# Maka_Niu_Endcap.net
KiCad netlist of a schematic drawn in EAGLE
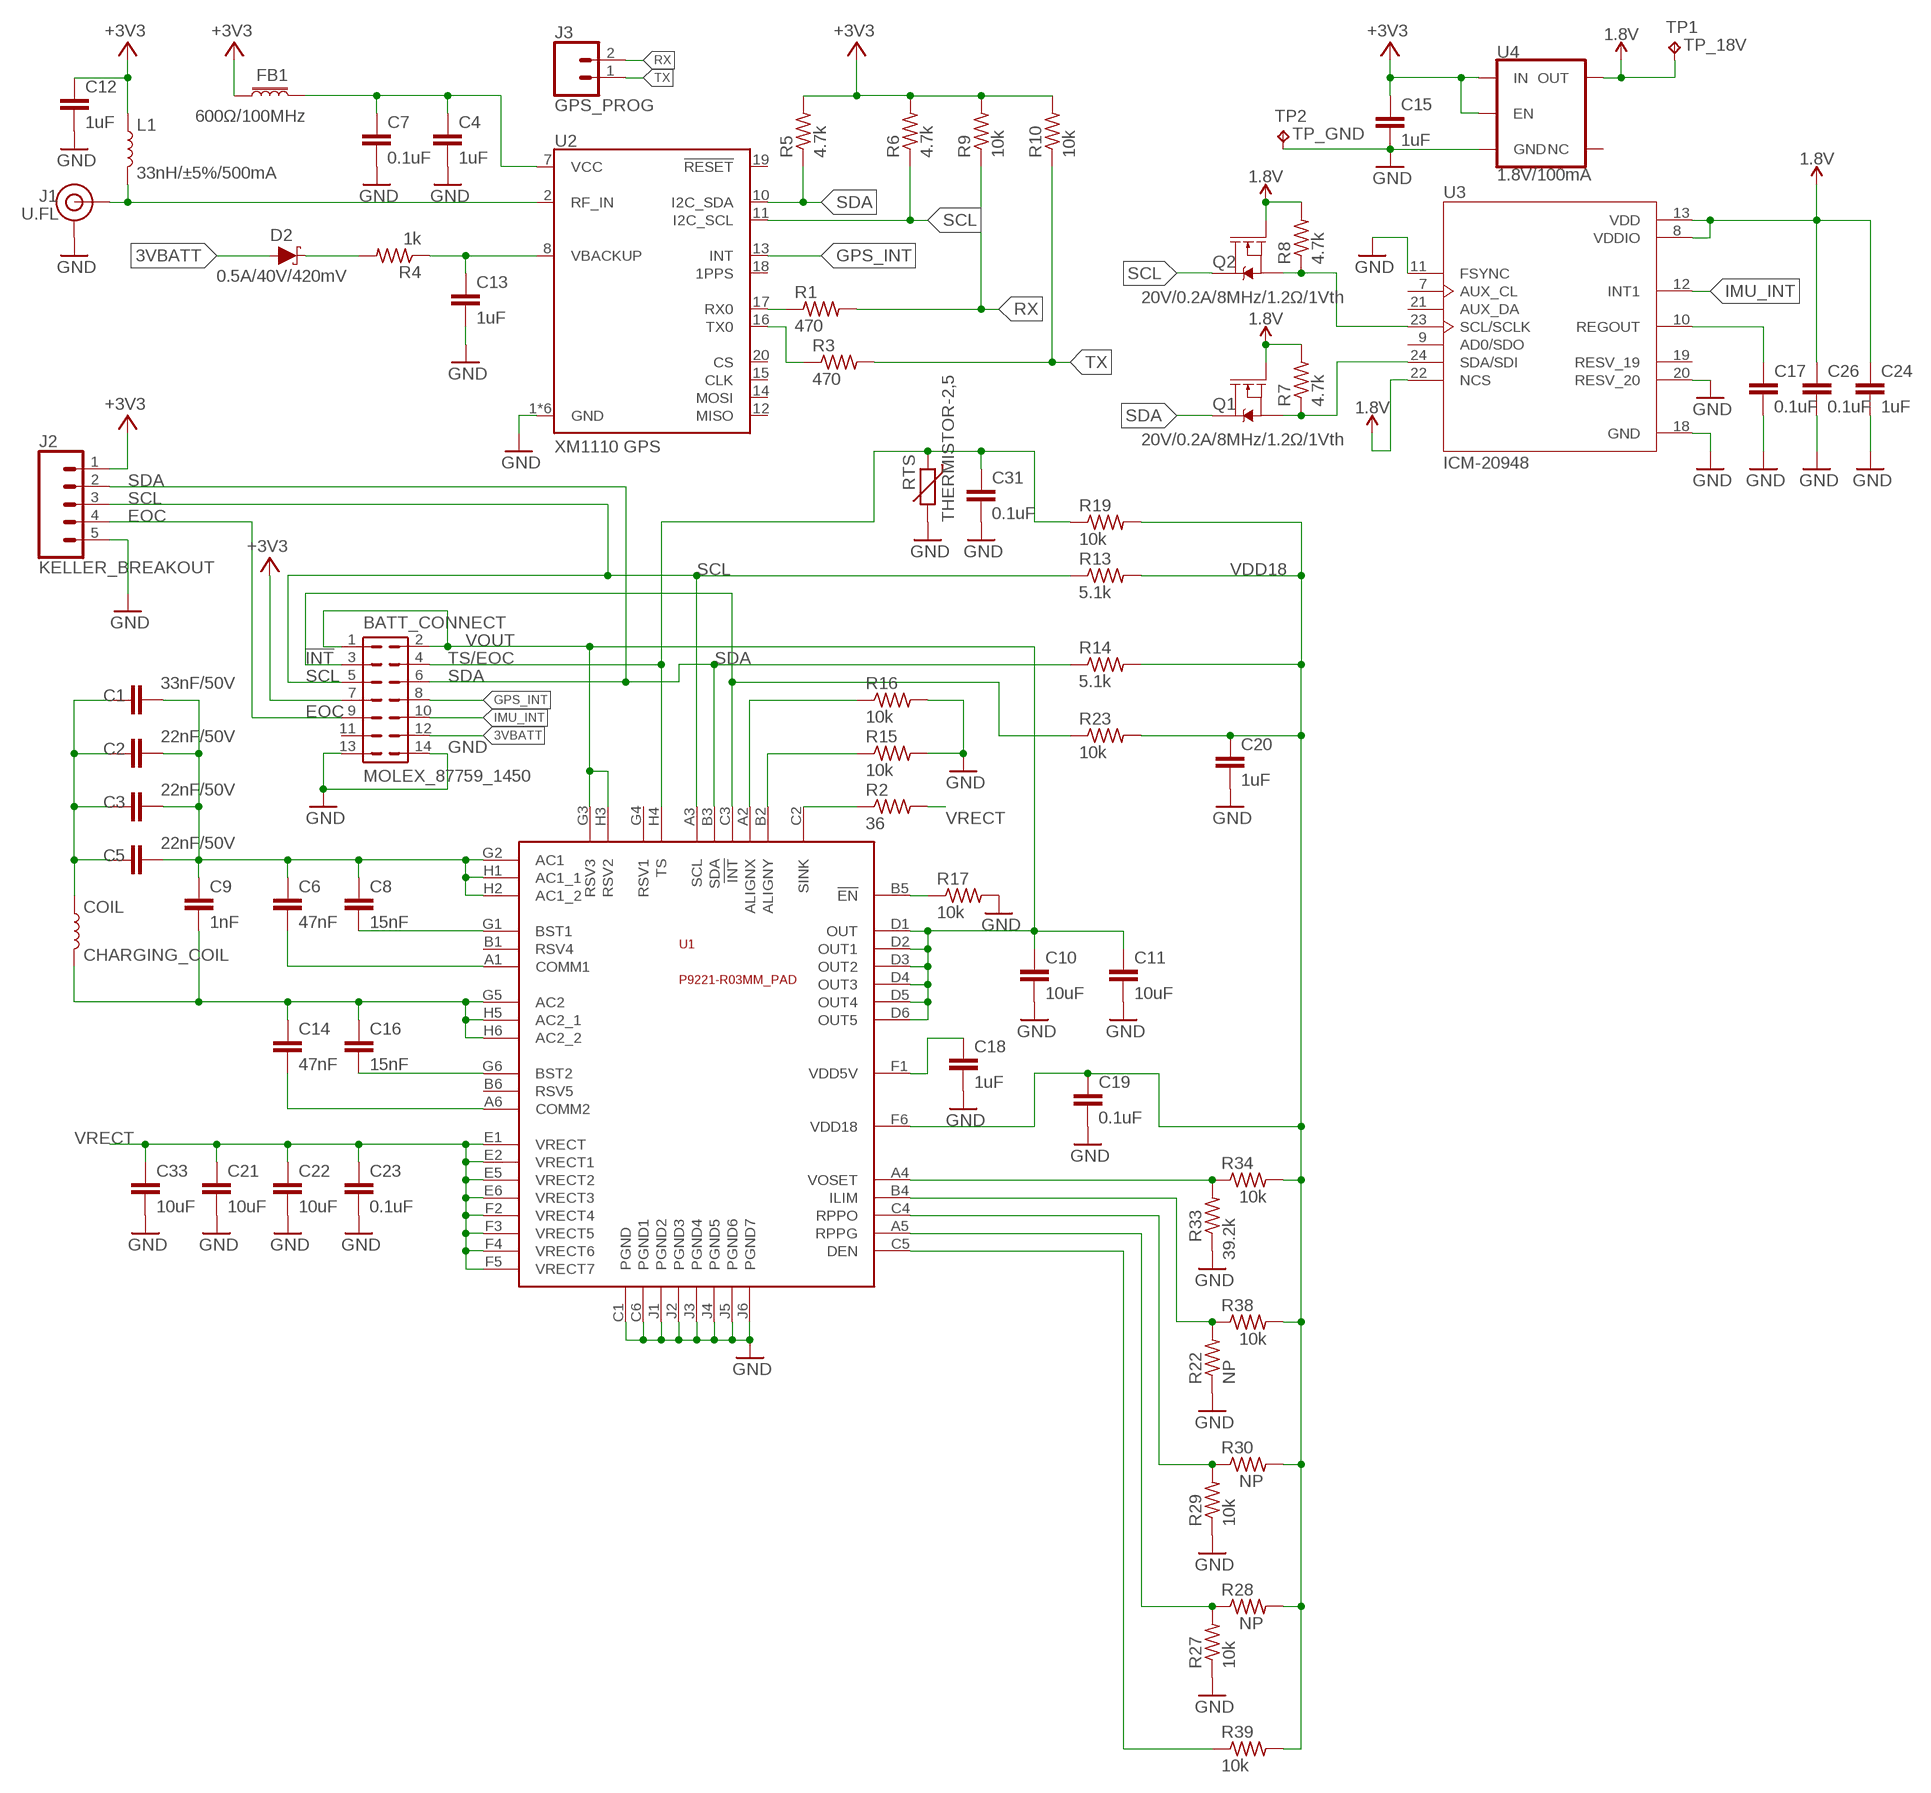
[diagram p0: schematic, sheet 1]

(export (version "E")
  (design (tool "Eeschema 10.0.6"))
  (components
    (comp (ref "BATT_CONNECT")
      (value "MOLEX_87759_1450")
      (footprint "eagle-import:87759-1450")
      (fields
        (field (name "DIGI-KEY_PART_NUMBER") "WM18654-ND")
        (field (name "MF") "MOLEX")
        (field (name "MP") "0877591450")
      )
      (libsource (lib "eagle-import") (part "MOLEX_87759_1450"))
    )
    (comp (ref "C1")
      (value "33nF/50V")
      (footprint "eagle-import:C0402")
      (fields
        (field (name "DIGI-KEY_PART_NUMBER") "490-13296-1-ND")
        (field (name "MF") "Murata Electronics")
        (field (name "MP") "GRM155R71H333KE02D")
      )
      (libsource (lib "eagle-import") (part "C-EUC0402"))
    )
    (comp (ref "C2")
      (value "22nF/50V")
      (footprint "eagle-import:C0402")
      (fields
        (field (name "DIGI-KEY_PART_NUMBER") "490-6360-1-ND")
        (field (name "MF") "Murata Electronics")
        (field (name "MP") "GRM155R71H223KA12J")
      )
      (libsource (lib "eagle-import") (part "C-EUC0402"))
    )
    (comp (ref "C3")
      (value "22nF/50V")
      (footprint "eagle-import:C0402")
      (fields
        (field (name "DIGI-KEY_PART_NUMBER") "490-6360-1-ND")
        (field (name "MF") "Murata Electronics")
        (field (name "MP") "GRM155R71H223KA12J")
      )
      (libsource (lib "eagle-import") (part "C-EUC0402"))
    )
    (comp (ref "C4")
      (value "1uF")
      (footprint "eagle-import:C0402")
      (fields
        (field (name "DIGI-KEY_PART_NUMBER") "311-1439-1-ND")
        (field (name "MF") "Yageo")
        (field (name "MP") "CC0402KRX5R6BB105")
      )
      (libsource (lib "eagle-import") (part "C-EUC0402"))
    )
    (comp (ref "C5")
      (value "22nF/50V")
      (footprint "eagle-import:C0402")
      (fields
        (field (name "DIGI-KEY_PART_NUMBER") "490-6360-1-ND")
        (field (name "MF") "Murata Electronics")
        (field (name "MP") "GRM155R71H223KA12J")
      )
      (libsource (lib "eagle-import") (part "C-EUC0402"))
    )
    (comp (ref "C6")
      (value "47nF")
      (footprint "eagle-import:C0402")
      (fields
        (field (name "DIGI-KEY_PART_NUMBER") "490-10702-1-ND")
        (field (name "MF") "Murata Electronics")
        (field (name "MP") "GRM155R71H473KE14D")
      )
      (libsource (lib "eagle-import") (part "C-EUC0402"))
    )
    (comp (ref "C7")
      (value "0.1uF")
      (footprint "eagle-import:C0402")
      (fields
        (field (name "DIGI-KEY_PART_NUMBER") "490-11917-1-ND")
        (field (name "MF") "Murata Electronics")
        (field (name "MP") "GRM155R61H104KE19D")
      )
      (libsource (lib "eagle-import") (part "C-EUC0402"))
    )
    (comp (ref "C8")
      (value "15nF")
      (footprint "eagle-import:C0402")
      (fields
        (field (name "DIGI-KEY_PART_NUMBER") "490-16428-1-ND")
        (field (name "MF") "Murata Electronics")
        (field (name "MP") "GCM155R71H153JA55D")
      )
      (libsource (lib "eagle-import") (part "C-EUC0402"))
    )
    (comp (ref "C9")
      (value "1nF")
      (footprint "eagle-import:C0402")
      (fields
        (field (name "DIGI-KEY_PART_NUMBER") "732-7556-1-ND")
        (field (name "MF") "Würth Elektronik")
        (field (name "MP") "885012205061 ")
      )
      (libsource (lib "eagle-import") (part "C-EUC0402"))
    )
    (comp (ref "C10")
      (value "10uF")
      (footprint "eagle-import:C_0603")
      (fields
        (field (name "DIGI-KEY_PART_NUMBER") "445-9015-1-ND")
        (field (name "MF") "TDK Corporation")
        (field (name "MP") "C1608X5R1E106M080AC")
      )
      (libsource (lib "eagle-import") (part "C0603C0603W"))
    )
    (comp (ref "C11")
      (value "10uF")
      (footprint "eagle-import:C_0603")
      (fields
        (field (name "DIGI-KEY_PART_NUMBER") "445-9015-1-ND")
        (field (name "MF") "TDK Corporation")
        (field (name "MP") "C1608X5R1E106M080AC")
      )
      (libsource (lib "eagle-import") (part "C0603C0603W"))
    )
    (comp (ref "C12")
      (value "1uF")
      (footprint "eagle-import:C0402")
      (fields
        (field (name "DIGI-KEY_PART_NUMBER") "311-1439-1-ND")
        (field (name "MF") "Yageo")
        (field (name "MP") "CC0402KRX5R6BB105")
      )
      (libsource (lib "eagle-import") (part "C-EUC0402"))
    )
    (comp (ref "C13")
      (value "1uF")
      (footprint "eagle-import:C0402")
      (fields
        (field (name "DIGI-KEY_PART_NUMBER") "311-1439-1-ND")
        (field (name "MF") "Yageo")
        (field (name "MP") "CC0402KRX5R6BB105")
      )
      (libsource (lib "eagle-import") (part "C-EUC0402"))
    )
    (comp (ref "C14")
      (value "47nF")
      (footprint "eagle-import:C0402")
      (fields
        (field (name "DIGI-KEY_PART_NUMBER") "490-10702-1-ND")
        (field (name "MF") "Murata Electronics")
        (field (name "MP") "GRM155R71H473KE14D")
      )
      (libsource (lib "eagle-import") (part "C-EUC0402"))
    )
    (comp (ref "C15")
      (value "1uF")
      (footprint "eagle-import:C0402")
      (fields
        (field (name "DIGI-KEY_PART_NUMBER") "311-1439-1-ND")
        (field (name "MF") "Yageo")
        (field (name "MP") "CC0402KRX5R6BB105")
      )
      (libsource (lib "eagle-import") (part "C-EUC0402"))
    )
    (comp (ref "C16")
      (value "15nF")
      (footprint "eagle-import:C0402")
      (fields
        (field (name "DIGI-KEY_PART_NUMBER") "490-16428-1-ND")
        (field (name "MF") "Murata Electronics")
        (field (name "MP") "GCM155R71H153JA55D")
      )
      (libsource (lib "eagle-import") (part "C-EUC0402"))
    )
    (comp (ref "C17")
      (value "0.1uF")
      (footprint "eagle-import:C0402")
      (fields
        (field (name "DIGI-KEY_PART_NUMBER") "490-11917-1-ND")
        (field (name "MF") "Murata Electronics")
        (field (name "MP") "GRM155R61H104KE19D")
      )
      (libsource (lib "eagle-import") (part "C-EUC0402"))
    )
    (comp (ref "C18")
      (value "1uF")
      (footprint "eagle-import:C0402")
      (fields
        (field (name "DIGI-KEY_PART_NUMBER") "311-1439-1-ND")
        (field (name "MF") "Yageo")
        (field (name "MP") "CC0402KRX5R6BB105")
      )
      (libsource (lib "eagle-import") (part "C-EUC0402"))
    )
    (comp (ref "C19")
      (value "0.1uF")
      (footprint "eagle-import:C0201")
      (fields
        (field (name "DIGI-KEY_PART_NUMBER") "445-7318-1-ND")
        (field (name "MF") "TDK Corporation")
        (field (name "MP") "C0603X5R1A104K030BC")
      )
      (libsource (lib "eagle-import") (part "C-EUC0201"))
    )
    (comp (ref "C20")
      (value "1uF")
      (footprint "eagle-import:C0402")
      (fields
        (field (name "DIGI-KEY_PART_NUMBER") "311-1439-1-ND")
        (field (name "MF") "Yageo")
        (field (name "MP") "CC0402KRX5R6BB105")
      )
      (libsource (lib "eagle-import") (part "C-EUC0402"))
    )
    (comp (ref "C21")
      (value "10uF")
      (footprint "eagle-import:C_0603")
      (fields
        (field (name "DIGI-KEY_PART_NUMBER") "445-9015-1-ND")
        (field (name "MF") "TDK Corporation")
        (field (name "MP") "C1608X5R1E106M080AC")
      )
      (libsource (lib "eagle-import") (part "C0603C0603W"))
    )
    (comp (ref "C22")
      (value "10uF")
      (footprint "eagle-import:C_0603")
      (fields
        (field (name "DIGI-KEY_PART_NUMBER") "445-9015-1-ND")
        (field (name "MF") "TDK Corporation")
        (field (name "MP") "C1608X5R1E106M080AC")
      )
      (libsource (lib "eagle-import") (part "C0603C0603W"))
    )
    (comp (ref "C23")
      (value "0.1uF")
      (footprint "eagle-import:C0201")
      (fields
        (field (name "DIGI-KEY_PART_NUMBER") "1276-1318-1-ND")
        (field (name "MF") "Samsung Electro-Mechanics")
        (field (name "MP") "CL03A104KA3NNNC")
      )
      (libsource (lib "eagle-import") (part "C-EUC0201"))
    )
    (comp (ref "C24")
      (value "1uF")
      (footprint "eagle-import:C0402")
      (fields
        (field (name "DIGI-KEY_PART_NUMBER") "311-1439-1-ND")
        (field (name "MF") "Yageo")
        (field (name "MP") "CC0402KRX5R6BB105")
      )
      (libsource (lib "eagle-import") (part "C-EUC0402"))
    )
    (comp (ref "C26")
      (value "0.1uF")
      (footprint "eagle-import:C0402")
      (fields
        (field (name "DIGI-KEY_PART_NUMBER") "490-11917-1-ND")
        (field (name "MF") "Murata Electronics")
        (field (name "MP") "GRM155R61H104KE19D")
      )
      (libsource (lib "eagle-import") (part "C-EUC0402"))
    )
    (comp (ref "C31")
      (value "0.1uF")
      (footprint "eagle-import:C0201")
      (fields
        (field (name "DIGI-KEY_PART_NUMBER") "445-7318-1-ND")
        (field (name "MF") "TDK Corporation")
        (field (name "MP") "C0603X5R1A104K030BC")
      )
      (libsource (lib "eagle-import") (part "C-EUC0201"))
    )
    (comp (ref "C33")
      (value "10uF")
      (footprint "eagle-import:C_0603")
      (fields
        (field (name "DIGI-KEY_PART_NUMBER") "445-9015-1-ND")
        (field (name "MF") "TDK Corporation")
        (field (name "MP") "C1608X5R1E106M080AC")
      )
      (libsource (lib "eagle-import") (part "C0603C0603W"))
    )
    (comp (ref "COIL")
      (value "CHARGING_COIL")
      (footprint "eagle-import:CHARGING_COIL")
      (libsource (lib "eagle-import") (part "CHARGING_COIL"))
    )
    (comp (ref "D2")
      (value "0.5A/40V/420mV")
      (footprint "eagle-import:SOD-323")
      (fields
        (field (name "DIGI-KEY_PART_NUMBER") "1727-5209-1-ND")
        (field (name "MF") "Nexperia USA Inc.")
        (field (name "MP") "PMEG4005AEA,115")
      )
      (libsource (lib "eagle-import") (part "DIODE-SCHOTTKY-PMEG4005EJ"))
    )
    (comp (ref "FB1")
      (value "600Ω/100MHz")
      (footprint "eagle-import:0603")
      (fields
        (field (name "DIGI-KEY_PART_NUMBER") "445-172898-1-ND")
        (field (name "MF") "TDK Corporation")
        (field (name "MP") "MPZ1608S601ATD25")
      )
      (libsource (lib "eagle-import") (part "FERRITE_BEAD-0603"))
    )
    (comp (ref "J1")
      (value "U.FL")
      (footprint "eagle-import:U.FL")
      (fields
        (field (name "DIGI-KEY_PART_NUMBER") "A144746CT-ND")
        (field (name "MF") "TE Connectivity AMP Connectors")
        (field (name "MP") "2337019-1")
      )
      (libsource (lib "eagle-import") (part "U.FL2PIN"))
    )
    (comp (ref "J2")
      (value "KELLER_BREAKOUT")
      (footprint "eagle-import:WIRES_2MM_05")
      (libsource (lib "eagle-import") (part "WIRES_2MM_05"))
    )
    (comp (ref "J3")
      (value "GPS_PROG")
      (footprint "eagle-import:WIRES_2MM_02SMD")
      (libsource (lib "eagle-import") (part "WIRES_2MM_02SMD"))
    )
    (comp (ref "L1")
      (value "33nH/±5%/500mA")
      (footprint "eagle-import:0603")
      (fields
        (field (name "DIGI-KEY_PART_NUMBER") "490-14837-1-ND")
        (field (name "MF") "Murata Electronics")
        (field (name "MP") "LQG18HH33NJ00D")
      )
      (libsource (lib "eagle-import") (part "INDUCTOR-0603-33NH"))
    )
    (comp (ref "Q1")
      (value "20V/0.2A/8MHz/1.2Ω/1Vth")
      (footprint "eagle-import:SOT-416FL")
      (fields
        (field (name "DIGI-KEY_PART_NUMBER") "RE1C002UNTCLCT-ND")
        (field (name "MF") "Rohm Semiconductor")
        (field (name "MP") "RE1C002UNTCL")
      )
      (libsource (lib "eagle-import") (part "MOSFET-NCH-RE1C00UNTL"))
    )
    (comp (ref "Q2")
      (value "20V/0.2A/8MHz/1.2Ω/1Vth")
      (footprint "eagle-import:SOT-416FL")
      (fields
        (field (name "DIGI-KEY_PART_NUMBER") "RE1C002UNTCLCT-ND")
        (field (name "MF") "Rohm Semiconductor")
        (field (name "MP") "RE1C002UNTCL")
      )
      (libsource (lib "eagle-import") (part "MOSFET-NCH-RE1C00UNTL"))
    )
    (comp (ref "R1")
      (value "470")
      (footprint "eagle-import:R0402")
      (fields
        (field (name "DIGI-KEY_PART_NUMBER") "RMCF0402JT470RCT-ND")
        (field (name "MF") "Stackpole Electronics Inc.")
        (field (name "MP") "RMCF0402JT470R")
      )
      (libsource (lib "eagle-import") (part "R-US_R0402"))
    )
    (comp (ref "R2")
      (value "36")
      (footprint "eagle-import:R0805")
      (fields
        (field (name "DIGI-KEY_PART_NUMBER") "P36ADCT-ND")
        (field (name "MF") "Panasonic Electronic Components")
        (field (name "MP") "ERJ-P06J360V")
      )
      (libsource (lib "eagle-import") (part "R-US_R0805"))
    )
    (comp (ref "R3")
      (value "470")
      (footprint "eagle-import:R0402")
      (fields
        (field (name "DIGI-KEY_PART_NUMBER") "RMCF0402JT470RCT-ND")
        (field (name "MF") "Stackpole Electronics Inc.")
        (field (name "MP") "RMCF0402JT470R")
      )
      (libsource (lib "eagle-import") (part "R-US_R0402"))
    )
    (comp (ref "R4")
      (value "1k")
      (footprint "eagle-import:R0402")
      (fields
        (field (name "DIGI-KEY_PART_NUMBER") "RMCF0402JT1K00CT-ND")
        (field (name "MF") "Stackpole Electronics Inc.")
        (field (name "MP") "RMCF0402JT1K00")
      )
      (libsource (lib "eagle-import") (part "R-US_R0402"))
    )
    (comp (ref "R5")
      (value "4.7k")
      (footprint "eagle-import:R0402")
      (fields
        (field (name "DIGI-KEY_PART_NUMBER") "RMCF0402JT4K70CT-ND")
        (field (name "MF") "Stackpole Electronics Inc.")
        (field (name "MP") "RMCF0402JT4K70")
      )
      (libsource (lib "eagle-import") (part "R-US_R0402"))
    )
    (comp (ref "R6")
      (value "4.7k")
      (footprint "eagle-import:R0402")
      (fields
        (field (name "DIGI-KEY_PART_NUMBER") "RMCF0402JT4K70CT-ND")
        (field (name "MF") "Stackpole Electronics Inc.")
        (field (name "MP") "RMCF0402JT4K70")
      )
      (libsource (lib "eagle-import") (part "R-US_R0402"))
    )
    (comp (ref "R7")
      (value "4.7k")
      (footprint "eagle-import:R0402")
      (fields
        (field (name "DIGI-KEY_PART_NUMBER") "RMCF0402JT4K70CT-ND")
        (field (name "MF") "Stackpole Electronics Inc.")
        (field (name "MP") "RMCF0402JT4K70")
      )
      (libsource (lib "eagle-import") (part "R-US_R0402"))
    )
    (comp (ref "R8")
      (value "4.7k")
      (footprint "eagle-import:R0402")
      (fields
        (field (name "DIGI-KEY_PART_NUMBER") "RMCF0402JT4K70CT-ND")
        (field (name "MF") "Stackpole Electronics Inc.")
        (field (name "MP") "RMCF0402JT4K70")
      )
      (libsource (lib "eagle-import") (part "R-US_R0402"))
    )
    (comp (ref "R9")
      (value "10k")
      (footprint "eagle-import:R0402")
      (fields
        (field (name "DIGI-KEY_PART_NUMBER") "RMCF0402JT10K0CT-ND")
        (field (name "MF") "Stackpole Electronics Inc.")
        (field (name "MP") "RMCF0402JT10K0")
      )
      (libsource (lib "eagle-import") (part "R-US_R0402"))
    )
    (comp (ref "R10")
      (value "10k")
      (footprint "eagle-import:R0402")
      (fields
        (field (name "DIGI-KEY_PART_NUMBER") "RMCF0402JT10K0CT-ND")
        (field (name "MF") "Stackpole Electronics Inc.")
        (field (name "MP") "RMCF0402JT10K0")
      )
      (libsource (lib "eagle-import") (part "R-US_R0402"))
    )
    (comp (ref "R13")
      (value "5.1k")
      (footprint "eagle-import:R0402")
      (fields
        (field (name "DIGI-KEY_PART_NUMBER") "CR0402-JW-512GLFCT-ND")
        (field (name "MF") "Bourns Inc.")
        (field (name "MP") "CR0402-JW-512GLF")
      )
      (libsource (lib "eagle-import") (part "R-US_R0402"))
    )
    (comp (ref "R14")
      (value "5.1k")
      (footprint "eagle-import:R0402")
      (fields
        (field (name "DIGI-KEY_PART_NUMBER") "CR0402-JW-512GLFCT-ND")
        (field (name "MF") "Bourns Inc.")
        (field (name "MP") "CR0402-JW-512GLF")
      )
      (libsource (lib "eagle-import") (part "R-US_R0402"))
    )
    (comp (ref "R15")
      (value "10k")
      (footprint "eagle-import:R_0603")
      (fields
        (field (name "DIGI-KEY_PART_NUMBER") "311-10.0KHRCT-ND")
        (field (name "MF") "Yageo")
        (field (name "MP") "RC0603FR-0710KL")
      )
      (libsource (lib "eagle-import") (part "R0603R0603W"))
    )
    (comp (ref "R16")
      (value "10k")
      (footprint "eagle-import:R_0603")
      (fields
        (field (name "DIGI-KEY_PART_NUMBER") "311-10.0KHRCT-ND")
        (field (name "MF") "Yageo")
        (field (name "MP") "RC0603FR-0710KL")
      )
      (libsource (lib "eagle-import") (part "R0603R0603W"))
    )
    (comp (ref "R17")
      (value "10k")
      (footprint "eagle-import:R0402")
      (fields
        (field (name "DIGI-KEY_PART_NUMBER") "541-10KATCT-ND")
        (field (name "MF") "Vishay Dale")
        (field (name "MP") "CRCW040210K0JNEDIF")
      )
      (libsource (lib "eagle-import") (part "R-US_R0402"))
    )
    (comp (ref "R19")
      (value "10k")
      (footprint "eagle-import:R0402")
      (fields
        (field (name "DIGI-KEY_PART_NUMBER") "541-10KATCT-ND")
        (field (name "MF") "Vishay Dale")
        (field (name "MP") "CRCW040210K0JNEDIF")
      )
      (libsource (lib "eagle-import") (part "R-US_R0402"))
    )
    (comp (ref "R22")
      (value "NP")
      (footprint "eagle-import:R0402")
      (libsource (lib "eagle-import") (part "R-US_R0402"))
    )
    (comp (ref "R23")
      (value "10k")
      (footprint "eagle-import:R0402")
      (fields
        (field (name "DIGI-KEY_PART_NUMBER") "541-10KATCT-ND")
        (field (name "MF") "Vishay Dale")
        (field (name "MP") "CRCW040210K0JNEDIF")
      )
      (libsource (lib "eagle-import") (part "R-US_R0402"))
    )
    (comp (ref "R27")
      (value "10k")
      (footprint "eagle-import:R0402")
      (fields
        (field (name "DIGI-KEY_PART_NUMBER") "541-10KATCT-ND")
        (field (name "MF") "Vishay Dale")
        (field (name "MP") "CRCW040210K0JNEDIF")
      )
      (libsource (lib "eagle-import") (part "R-US_R0402"))
    )
    (comp (ref "R28")
      (value "NP")
      (footprint "eagle-import:R0402")
      (libsource (lib "eagle-import") (part "R-US_R0402"))
    )
    (comp (ref "R29")
      (value "10k")
      (footprint "eagle-import:R0402")
      (fields
        (field (name "DIGI-KEY_PART_NUMBER") "541-10KATCT-ND")
        (field (name "MF") "Vishay Dale")
        (field (name "MP") "CRCW040210K0JNEDIF")
      )
      (libsource (lib "eagle-import") (part "R-US_R0402"))
    )
    (comp (ref "R30")
      (value "NP")
      (footprint "eagle-import:R0402")
      (libsource (lib "eagle-import") (part "R-US_R0402"))
    )
    (comp (ref "R33")
      (value "39.2k")
      (footprint "eagle-import:R0402")
      (fields
        (field (name "DIGI-KEY_PART_NUMBER") "311-39.2KLBCT-ND")
        (field (name "MF") "Yageo")
        (field (name "MP") "AC0402FR-0739K2L")
      )
      (libsource (lib "eagle-import") (part "R-US_R0402"))
    )
    (comp (ref "R34")
      (value "10k")
      (footprint "eagle-import:R0402")
      (fields
        (field (name "DIGI-KEY_PART_NUMBER") "541-10KATCT-ND")
        (field (name "MF") "Vishay Dale")
        (field (name "MP") "CRCW040210K0JNEDIF")
      )
      (libsource (lib "eagle-import") (part "R-US_R0402"))
    )
    (comp (ref "R38")
      (value "10k")
      (footprint "eagle-import:R0402")
      (fields
        (field (name "DIGI-KEY_PART_NUMBER") "541-10KATCT-ND")
        (field (name "MF") "Vishay Dale")
        (field (name "MP") "CRCW040210K0JNEDIF")
      )
      (libsource (lib "eagle-import") (part "R-US_R0402"))
    )
    (comp (ref "R39")
      (value "10k")
      (footprint "eagle-import:R0402")
      (fields
        (field (name "DIGI-KEY_PART_NUMBER") "541-10KATCT-ND")
        (field (name "MF") "Vishay Dale")
        (field (name "MP") "CRCW040210K0JNEDIF")
      )
      (libsource (lib "eagle-import") (part "R-US_R0402"))
    )
    (comp (ref "RTS")
      (value "THERMISTOR-2,5")
      (footprint "eagle-import:RS-2,5")
      (libsource (lib "eagle-import") (part "THERMISTOR-2,5"))
    )
    (comp (ref "TP1")
      (value "TP_18V")
      (footprint "eagle-import:B1,27")
      (fields (field (name "TP_SIGNAL_NAME") "TP_18V"))
      (libsource (lib "eagle-import") (part "TPB1,27"))
    )
    (comp (ref "TP2")
      (value "TP_GND")
      (footprint "eagle-import:B1,27")
      (fields (field (name "TP_SIGNAL_NAME") "TP_GND"))
      (libsource (lib "eagle-import") (part "TPB1,27"))
    )
    (comp (ref "U1")
      (value "P9221-R03MM_PAD")
      (footprint "eagle-import:CSP52_2P64X3P94_0P4MM_03MMPAD")
      (fields
        (field (name "DIGI-KEY_PART_NUMBER") "800-3932-2-ND")
        (field (name "MF") "Renesas Electronics America Inc.")
        (field (name "MP") "P9221-RAHGI8")
      )
      (libsource (lib "eagle-import") (part "P9221-R03MM_PAD"))
    )
    (comp (ref "U2")
      (value "XM1110 GPS")
      (footprint "eagle-import:XM1110_GPS")
      (fields
        (field (name "DIGI-KEY_PART_NUMBER") "1645-XM1110_1104311CT-ND")
        (field (name "MF") "Sierra Wireless")
        (field (name "MP") "XM1110_1104311")
      )
      (libsource (lib "eagle-import") (part "XM1110_GPS"))
    )
    (comp (ref "U3")
      (value "ICM-20948")
      (footprint "eagle-import:QFN40P300X300X105-24N")
      (fields (field (name "DIGI-KEY_PART_NUMBER") "1428-1123-1-ND") (field (name "MF") "TDK InvenSense"))
      (libsource (lib "eagle-import") (part "ICM-20948"))
    )
    (comp (ref "U4")
      (value "1.8V/100mA")
      (footprint "eagle-import:SC70")
      (fields
        (field (name "DIGI-KEY_PART_NUMBER") "576-2807-1-ND")
        (field (name "MF") "Microchip Technology")
        (field (name "MP") "MIC5253-1.8YC5-TR")
      )
      (libsource (lib "eagle-import") (part "V_REG_SP6214-1.8V"))
    )
  )
  (nets
    (net (code "1") (name "+3V3") (class "Default")
      (node (ref "BATT_CONNECT") (pin "7") (pinfunction "7_7") (pintype "passive"))
      (node (ref "C12") (pin "1") (pinfunction "1_1") (pintype "passive"))
      (node (ref "C15") (pin "1") (pinfunction "1_1") (pintype "passive"))
      (node (ref "FB1") (pin "1") (pinfunction "1_1") (pintype "passive"))
      (node (ref "J2") (pin "1") (pinfunction "1_1") (pintype "passive"))
      (node (ref "L1") (pin "1") (pinfunction "1_1") (pintype "passive"))
      (node (ref "R10") (pin "2") (pinfunction "2_2") (pintype "passive"))
      (node (ref "R5") (pin "2") (pinfunction "2_2") (pintype "passive"))
      (node (ref "R6") (pin "2") (pinfunction "2_2") (pintype "passive"))
      (node (ref "R9") (pin "2") (pinfunction "2_2") (pintype "passive"))
      (node (ref "U4") (pin "1") (pinfunction "IN_1") (pintype "input"))
      (node (ref "U4") (pin "3") (pinfunction "EN_3") (pintype "input"))
    )
    (net (code "2") (name "/EOC") (class "Default")
      (node (ref "BATT_CONNECT") (pin "9") (pinfunction "9_9") (pintype "passive"))
      (node (ref "J2") (pin "4") (pinfunction "4_4") (pintype "passive"))
    )
    (net (code "3") (name "/TS{slash}EOC") (class "Default")
      (node (ref "BATT_CONNECT") (pin "4") (pinfunction "4_4") (pintype "passive"))
      (node (ref "C31") (pin "1") (pinfunction "1_1") (pintype "passive"))
      (node (ref "R19") (pin "1") (pinfunction "1_1") (pintype "passive"))
      (node (ref "RTS") (pin "1") (pinfunction "1_1") (pintype "passive"))
      (node (ref "U1") (pin "H4") (pinfunction "TS_H4") (pintype "input"))
    )
    (net (code "4") (name "/VDD18") (class "Default")
      (node (ref "C19") (pin "1") (pinfunction "1_1") (pintype "passive"))
      (node (ref "C20") (pin "1") (pinfunction "1_1") (pintype "passive"))
      (node (ref "R13") (pin "2") (pinfunction "2_2") (pintype "passive"))
      (node (ref "R14") (pin "2") (pinfunction "2_2") (pintype "passive"))
      (node (ref "R19") (pin "2") (pinfunction "2_2") (pintype "passive"))
      (node (ref "R23") (pin "2") (pinfunction "2_2") (pintype "passive"))
      (node (ref "R28") (pin "2") (pinfunction "2_2") (pintype "passive"))
      (node (ref "R30") (pin "2") (pinfunction "2_2") (pintype "passive"))
      (node (ref "R34") (pin "2") (pinfunction "2_2") (pintype "passive"))
      (node (ref "R38") (pin "2") (pinfunction "2_2") (pintype "passive"))
      (node (ref "R39") (pin "2") (pinfunction "2_2") (pintype "passive"))
      (node (ref "U1") (pin "F6") (pinfunction "VDD18_F6") (pintype "output"))
    )
    (net (code "5") (name "/VOUT") (class "Default")
      (node (ref "BATT_CONNECT") (pin "1") (pinfunction "1_1") (pintype "passive"))
      (node (ref "BATT_CONNECT") (pin "2") (pinfunction "2_2") (pintype "passive"))
      (node (ref "C10") (pin "1") (pinfunction "1_1") (pintype "passive"))
      (node (ref "C11") (pin "1") (pinfunction "1_1") (pintype "passive"))
      (node (ref "U1") (pin "D1") (pinfunction "OUT_D1") (pintype "output"))
      (node (ref "U1") (pin "D2") (pinfunction "OUT1_D2") (pintype "output"))
      (node (ref "U1") (pin "D3") (pinfunction "OUT2_D3") (pintype "output"))
      (node (ref "U1") (pin "D4") (pinfunction "OUT3_D4") (pintype "output"))
      (node (ref "U1") (pin "D5") (pinfunction "OUT4_D5") (pintype "output"))
      (node (ref "U1") (pin "D6") (pinfunction "OUT5_D6") (pintype "output"))
      (node (ref "U1") (pin "G3") (pinfunction "RSV3_G3") (pintype "input"))
      (node (ref "U1") (pin "H3") (pinfunction "RSV2_H3") (pintype "input"))
    )
    (net (code "6") (name "/VRECT") (class "Default")
      (node (ref "C21") (pin "1") (pinfunction "1_1") (pintype "passive"))
      (node (ref "C22") (pin "1") (pinfunction "1_1") (pintype "passive"))
      (node (ref "C23") (pin "1") (pinfunction "1_1") (pintype "passive"))
      (node (ref "C33") (pin "1") (pinfunction "1_1") (pintype "passive"))
      (node (ref "R2") (pin "2") (pinfunction "2_2") (pintype "passive"))
      (node (ref "U1") (pin "E1") (pinfunction "VRECT_E1") (pintype "output"))
      (node (ref "U1") (pin "E2") (pinfunction "VRECT1_E2") (pintype "output"))
      (node (ref "U1") (pin "E5") (pinfunction "VRECT2_E5") (pintype "output"))
      (node (ref "U1") (pin "E6") (pinfunction "VRECT3_E6") (pintype "output"))
      (node (ref "U1") (pin "F2") (pinfunction "VRECT4_F2") (pintype "output"))
      (node (ref "U1") (pin "F3") (pinfunction "VRECT5_F3") (pintype "output"))
      (node (ref "U1") (pin "F4") (pinfunction "VRECT6_F4") (pintype "output"))
      (node (ref "U1") (pin "F5") (pinfunction "VRECT7_F5") (pintype "output"))
    )
    (net (code "7") (name "/~{INT}") (class "Default")
      (node (ref "BATT_CONNECT") (pin "3") (pinfunction "3_3") (pintype "passive"))
      (node (ref "R23") (pin "1") (pinfunction "1_1") (pintype "passive"))
      (node (ref "U1") (pin "C3") (pinfunction "~{INT}_C3") (pintype "output"))
    )
    (net (code "8") (name "1.8V") (class "Default")
      (node (ref "C24") (pin "1") (pinfunction "1_1") (pintype "passive"))
      (node (ref "C26") (pin "1") (pinfunction "1_1") (pintype "passive"))
      (node (ref "Q1") (pin "1") (pinfunction "G_1") (pintype "bidirectional"))
      (node (ref "Q2") (pin "1") (pinfunction "G_1") (pintype "bidirectional"))
      (node (ref "R7") (pin "2") (pinfunction "2_2") (pintype "passive"))
      (node (ref "R8") (pin "2") (pinfunction "2_2") (pintype "passive"))
      (node (ref "TP1") (pin "TP") (pinfunction "TP_TP") (pintype "input"))
      (node (ref "U3") (pin "13") (pinfunction "VDD_13") (pintype "power_in"))
      (node (ref "U3") (pin "22") (pinfunction "NCS_22") (pintype "input"))
      (node (ref "U3") (pin "8") (pinfunction "VDDIO_8") (pintype "power_in"))
      (node (ref "U4") (pin "5") (pinfunction "OUT_5") (pintype "passive"))
    )
    (net (code "9") (name "3VBATT") (class "Default")
      (node (ref "BATT_CONNECT") (pin "12") (pinfunction "12_12") (pintype "passive"))
      (node (ref "D2") (pin "A") (pinfunction "A_A") (pintype "passive"))
    )
    (net (code "10") (name "GND") (class "Default")
      (node (ref "BATT_CONNECT") (pin "13") (pinfunction "13_13") (pintype "passive"))
      (node (ref "BATT_CONNECT") (pin "14") (pinfunction "14_14") (pintype "passive"))
      (node (ref "C10") (pin "2") (pinfunction "2_2") (pintype "passive"))
      (node (ref "C11") (pin "2") (pinfunction "2_2") (pintype "passive"))
      (node (ref "C12") (pin "2") (pinfunction "2_2") (pintype "passive"))
      (node (ref "C13") (pin "2") (pinfunction "2_2") (pintype "passive"))
      (node (ref "C15") (pin "2") (pinfunction "2_2") (pintype "passive"))
      (node (ref "C17") (pin "2") (pinfunction "2_2") (pintype "passive"))
      (node (ref "C18") (pin "2") (pinfunction "2_2") (pintype "passive"))
      (node (ref "C19") (pin "2") (pinfunction "2_2") (pintype "passive"))
      (node (ref "C20") (pin "2") (pinfunction "2_2") (pintype "passive"))
      (node (ref "C21") (pin "2") (pinfunction "2_2") (pintype "passive"))
      (node (ref "C22") (pin "2") (pinfunction "2_2") (pintype "passive"))
      (node (ref "C23") (pin "2") (pinfunction "2_2") (pintype "passive"))
      (node (ref "C24") (pin "2") (pinfunction "2_2") (pintype "passive"))
      (node (ref "C26") (pin "2") (pinfunction "2_2") (pintype "passive"))
      (node (ref "C31") (pin "2") (pinfunction "2_2") (pintype "passive"))
      (node (ref "C33") (pin "2") (pinfunction "2_2") (pintype "passive"))
      (node (ref "C4") (pin "2") (pinfunction "2_2") (pintype "passive"))
      (node (ref "C7") (pin "2") (pinfunction "2_2") (pintype "passive"))
      (node (ref "J1") (pin "1") (pinfunction "GND_1") (pintype "bidirectional"))
      (node (ref "J1") (pin "2") (pinfunction "GND_2") (pintype "bidirectional"))
      (node (ref "J2") (pin "5") (pinfunction "5_5") (pintype "passive"))
      (node (ref "R15") (pin "2") (pinfunction "2_2") (pintype "passive"))
      (node (ref "R16") (pin "2") (pinfunction "2_2") (pintype "passive"))
      (node (ref "R17") (pin "2") (pinfunction "2_2") (pintype "passive"))
      (node (ref "R22") (pin "1") (pinfunction "1_1") (pintype "passive"))
      (node (ref "R27") (pin "1") (pinfunction "1_1") (pintype "passive"))
      (node (ref "R29") (pin "1") (pinfunction "1_1") (pintype "passive"))
      (node (ref "R33") (pin "1") (pinfunction "1_1") (pintype "passive"))
      (node (ref "RTS") (pin "2") (pinfunction "2_2") (pintype "passive"))
      (node (ref "TP2") (pin "TP") (pinfunction "TP_TP") (pintype "input"))
      (node (ref "U1") (pin "C1") (pinfunction "PGND_C1") (pintype "power_in"))
      (node (ref "U1") (pin "C6") (pinfunction "PGND1_C6") (pintype "power_in"))
      (node (ref "U1") (pin "J1") (pinfunction "PGND2_J1") (pintype "power_in"))
      (node (ref "U1") (pin "J2") (pinfunction "PGND3_J2") (pintype "power_in"))
      (node (ref "U1") (pin "J3") (pinfunction "PGND4_J3") (pintype "power_in"))
      (node (ref "U1") (pin "J4") (pinfunction "PGND5_J4") (pintype "power_in"))
      (node (ref "U1") (pin "J5") (pinfunction "PGND6_J5") (pintype "power_in"))
      (node (ref "U1") (pin "J6") (pinfunction "PGND7_J6") (pintype "power_in"))
      (node (ref "U2") (pin "1") (pinfunction "GND_1") (pintype "power_in"))
      (node (ref "U2") (pin "3") (pinfunction "GND_3") (pintype "power_in"))
      (node (ref "U2") (pin "4") (pinfunction "GND_4") (pintype "power_in"))
      (node (ref "U2") (pin "5") (pinfunction "GND_5") (pintype "power_in"))
      (node (ref "U2") (pin "6") (pinfunction "GND_6") (pintype "power_in"))
      (node (ref "U2") (pin "9") (pinfunction "GND_9") (pintype "power_in"))
      (node (ref "U3") (pin "11") (pinfunction "FSYNC_11") (pintype "input"))
      (node (ref "U3") (pin "18") (pinfunction "GND_18") (pintype "power_in"))
      (node (ref "U3") (pin "20") (pinfunction "RESV_20_20") (pintype "passive"))
      (node (ref "U4") (pin "2") (pinfunction "GND_2") (pintype "input"))
    )
    (net (code "11") (name "GPS_INT") (class "Default")
      (node (ref "BATT_CONNECT") (pin "8") (pinfunction "8_8") (pintype "passive"))
      (node (ref "U2") (pin "13") (pinfunction "INT_13") (pintype "output"))
    )
    (net (code "12") (name "IMU_INT") (class "Default")
      (node (ref "BATT_CONNECT") (pin "10") (pinfunction "10_10") (pintype "passive"))
      (node (ref "U3") (pin "12") (pinfunction "INT1_12") (pintype "output"))
    )
    (net (code "13") (name "Net-(COIL-1)") (class "Default")
      (node (ref "C1") (pin "1") (pinfunction "1_1") (pintype "passive"))
      (node (ref "C2") (pin "1") (pinfunction "1_1") (pintype "passive"))
      (node (ref "C3") (pin "1") (pinfunction "1_1") (pintype "passive"))
      (node (ref "C5") (pin "1") (pinfunction "1_1") (pintype "passive"))
      (node (ref "COIL") (pin "B1") (pinfunction "1_B1") (pintype "passive"))
    )
    (net (code "14") (name "Net-(COIL-2)") (class "Default")
      (node (ref "C14") (pin "1") (pinfunction "1_1") (pintype "passive"))
      (node (ref "C16") (pin "1") (pinfunction "1_1") (pintype "passive"))
      (node (ref "C9") (pin "2") (pinfunction "2_2") (pintype "passive"))
      (node (ref "COIL") (pin "B2") (pinfunction "2_B2") (pintype "passive"))
      (node (ref "U1") (pin "G5") (pinfunction "AC2_G5") (pintype "input"))
      (node (ref "U1") (pin "H5") (pinfunction "AC2_1_H5") (pintype "input"))
      (node (ref "U1") (pin "H6") (pinfunction "AC2_2_H6") (pintype "input"))
    )
    (net (code "15") (name "Net-(D2-PadC)") (class "Default")
      (node (ref "D2") (pin "C") (pinfunction "C_C") (pintype "passive"))
      (node (ref "R4") (pin "2") (pinfunction "2_2") (pintype "passive"))
    )
    (net (code "16") (name "Net-(J1-SIGNAL)") (class "Default")
      (node (ref "J1") (pin "FEED") (pinfunction "SIGNAL_FEED") (pintype "bidirectional"))
      (node (ref "L1") (pin "2") (pinfunction "2_2") (pintype "passive"))
      (node (ref "U2") (pin "2") (pinfunction "RF_IN_2") (pintype "input"))
    )
    (net (code "17") (name "Net-(Q1-S)") (class "Default")
      (node (ref "Q1") (pin "2") (pinfunction "S_2") (pintype "bidirectional"))
      (node (ref "R7") (pin "1") (pinfunction "1_1") (pintype "passive"))
      (node (ref "U3") (pin "24") (pinfunction "SDA/SDI_24") (pintype "bidirectional"))
    )
    (net (code "18") (name "Net-(Q2-S)") (class "Default")
      (node (ref "Q2") (pin "2") (pinfunction "S_2") (pintype "bidirectional"))
      (node (ref "R8") (pin "1") (pinfunction "1_1") (pintype "passive"))
      (node (ref "U3") (pin "23") (pinfunction "SCL/SCLK_23") (pintype "input"))
    )
    (net (code "19") (name "Net-(U1-AC1)") (class "Default")
      (node (ref "C1") (pin "2") (pinfunction "2_2") (pintype "passive"))
      (node (ref "C2") (pin "2") (pinfunction "2_2") (pintype "passive"))
      (node (ref "C3") (pin "2") (pinfunction "2_2") (pintype "passive"))
      (node (ref "C5") (pin "2") (pinfunction "2_2") (pintype "passive"))
      (node (ref "C6") (pin "1") (pinfunction "1_1") (pintype "passive"))
      (node (ref "C8") (pin "1") (pinfunction "1_1") (pintype "passive"))
      (node (ref "C9") (pin "1") (pinfunction "1_1") (pintype "passive"))
      (node (ref "U1") (pin "G2") (pinfunction "AC1_G2") (pintype "input"))
      (node (ref "U1") (pin "H1") (pinfunction "AC1_1_H1") (pintype "input"))
      (node (ref "U1") (pin "H2") (pinfunction "AC1_2_H2") (pintype "input"))
    )
    (net (code "20") (name "Net-(U1-ALIGNX)") (class "Default")
      (node (ref "R16") (pin "1") (pinfunction "1_1") (pintype "passive"))
      (node (ref "U1") (pin "A2") (pinfunction "ALIGNX_A2") (pintype "input"))
    )
    (net (code "21") (name "Net-(U1-ALIGNY)") (class "Default")
      (node (ref "R15") (pin "1") (pinfunction "1_1") (pintype "passive"))
      (node (ref "U1") (pin "B2") (pinfunction "ALIGNY_B2") (pintype "input"))
    )
    (net (code "22") (name "Net-(U1-BST1)") (class "Default")
      (node (ref "C8") (pin "2") (pinfunction "2_2") (pintype "passive"))
      (node (ref "U1") (pin "G1") (pinfunction "BST1_G1") (pintype "output"))
    )
    (net (code "23") (name "Net-(U1-BST2)") (class "Default")
      (node (ref "C16") (pin "2") (pinfunction "2_2") (pintype "passive"))
      (node (ref "U1") (pin "G6") (pinfunction "BST2_G6") (pintype "output"))
    )
    (net (code "24") (name "Net-(U1-COMM1)") (class "Default")
      (node (ref "C6") (pin "2") (pinfunction "2_2") (pintype "passive"))
      (node (ref "U1") (pin "A1") (pinfunction "COMM1_A1") (pintype "output"))
    )
    (net (code "25") (name "Net-(U1-COMM2)") (class "Default")
      (node (ref "C14") (pin "2") (pinfunction "2_2") (pintype "passive"))
      (node (ref "U1") (pin "A6") (pinfunction "COMM2_A6") (pintype "output"))
    )
    (net (code "26") (name "Net-(U1-DEN)") (class "Default")
      (node (ref "R39") (pin "1") (pinfunction "1_1") (pintype "passive"))
      (node (ref "U1") (pin "C5") (pinfunction "DEN_C5") (pintype "input"))
    )
    (net (code "27") (name "Net-(U1-ILIM)") (class "Default")
      (node (ref "R22") (pin "2") (pinfunction "2_2") (pintype "passive"))
      (node (ref "R38") (pin "1") (pinfunction "1_1") (pintype "passive"))
      (node (ref "U1") (pin "B4") (pinfunction "ILIM_B4") (pintype "input"))
    )
    (net (code "28") (name "Net-(U1-RPPG)") (class "Default")
      (node (ref "R27") (pin "2") (pinfunction "2_2") (pintype "passive"))
      (node (ref "R28") (pin "1") (pinfunction "1_1") (pintype "passive"))
      (node (ref "U1") (pin "A5") (pinfunction "RPPG_A5") (pintype "input"))
    )
    (net (code "29") (name "Net-(U1-RPPO)") (class "Default")
      (node (ref "R29") (pin "2") (pinfunction "2_2") (pintype "passive"))
      (node (ref "R30") (pin "1") (pinfunction "1_1") (pintype "passive"))
      (node (ref "U1") (pin "C4") (pinfunction "RPPO_C4") (pintype "input"))
    )
    (net (code "30") (name "Net-(U1-SINK)") (class "Default")
      (node (ref "R2") (pin "1") (pinfunction "1_1") (pintype "passive"))
      (node (ref "U1") (pin "C2") (pinfunction "SINK_C2") (pintype "output"))
    )
    (net (code "31") (name "Net-(U1-VDD5V)") (class "Default")
      (node (ref "C18") (pin "1") (pinfunction "1_1") (pintype "passive"))
      (node (ref "U1") (pin "F1") (pinfunction "VDD5V_F1") (pintype "output"))
    )
    (net (code "32") (name "Net-(U1-VOSET)") (class "Default")
      (node (ref "R33") (pin "2") (pinfunction "2_2") (pintype "passive"))
      (node (ref "R34") (pin "1") (pinfunction "1_1") (pintype "passive"))
      (node (ref "U1") (pin "A4") (pinfunction "VOSET_A4") (pintype "input"))
    )
    (net (code "33") (name "Net-(U1-~{EN})") (class "Default")
      (node (ref "R17") (pin "1") (pinfunction "1_1") (pintype "passive"))
      (node (ref "U1") (pin "B5") (pinfunction "~{EN}_B5") (pintype "input"))
    )
    (net (code "34") (name "Net-(U2-RX0)") (class "Default")
      (node (ref "R1") (pin "1") (pinfunction "1_1") (pintype "passive"))
      (node (ref "U2") (pin "17") (pinfunction "RX0_17") (pintype "input"))
    )
    (net (code "35") (name "Net-(U2-TX0)") (class "Default")
      (node (ref "R3") (pin "1") (pinfunction "1_1") (pintype "passive"))
      (node (ref "U2") (pin "16") (pinfunction "TX0_16") (pintype "output"))
    )
    (net (code "36") (name "Net-(U2-VBACKUP)") (class "Default")
      (node (ref "C13") (pin "1") (pinfunction "1_1") (pintype "passive"))
      (node (ref "R4") (pin "1") (pinfunction "1_1") (pintype "passive"))
      (node (ref "U2") (pin "8") (pinfunction "VBACKUP_8") (pintype "input"))
    )
    (net (code "37") (name "Net-(U2-VCC)") (class "Default")
      (node (ref "C4") (pin "1") (pinfunction "1_1") (pintype "passive"))
      (node (ref "C7") (pin "1") (pinfunction "1_1") (pintype "passive"))
      (node (ref "FB1") (pin "2") (pinfunction "2_2") (pintype "passive"))
      (node (ref "U2") (pin "7") (pinfunction "VCC_7") (pintype "power_in"))
    )
    (net (code "38") (name "Net-(U3-REGOUT)") (class "Default")
      (node (ref "C17") (pin "1") (pinfunction "1_1") (pintype "passive"))
      (node (ref "U3") (pin "10") (pinfunction "REGOUT_10") (pintype "output"))
    )
    (net (code "39") (name "RX") (class "Default")
      (node (ref "J3") (pin "2") (pinfunction "2_2") (pintype "passive"))
      (node (ref "R1") (pin "2") (pinfunction "2_2") (pintype "passive"))
      (node (ref "R9") (pin "1") (pinfunction "1_1") (pintype "passive"))
    )
    (net (code "40") (name "SCL") (class "Default")
      (node (ref "BATT_CONNECT") (pin "5") (pinfunction "5_5") (pintype "passive"))
      (node (ref "J2") (pin "3") (pinfunction "3_3") (pintype "passive"))
      (node (ref "Q2") (pin "3") (pinfunction "D_3") (pintype "bidirectional"))
      (node (ref "R13") (pin "1") (pinfunction "1_1") (pintype "passive"))
      (node (ref "R6") (pin "1") (pinfunction "1_1") (pintype "passive"))
      (node (ref "U1") (pin "A3") (pinfunction "SCL_A3") (pintype "input"))
      (node (ref "U2") (pin "11") (pinfunction "I2C_SCL_11") (pintype "input"))
    )
    (net (code "41") (name "SDA") (class "Default")
      (node (ref "BATT_CONNECT") (pin "6") (pinfunction "6_6") (pintype "passive"))
      (node (ref "J2") (pin "2") (pinfunction "2_2") (pintype "passive"))
      (node (ref "Q1") (pin "3") (pinfunction "D_3") (pintype "bidirectional"))
      (node (ref "R14") (pin "1") (pinfunction "1_1") (pintype "passive"))
      (node (ref "R5") (pin "1") (pinfunction "1_1") (pintype "passive"))
      (node (ref "U1") (pin "B3") (pinfunction "SDA_B3") (pintype "bidirectional"))
      (node (ref "U2") (pin "10") (pinfunction "I2C_SDA_10") (pintype "bidirectional"))
    )
    (net (code "42") (name "TX") (class "Default")
      (node (ref "J3") (pin "1") (pinfunction "1_1") (pintype "passive"))
      (node (ref "R10") (pin "1") (pinfunction "1_1") (pintype "passive"))
      (node (ref "R3") (pin "2") (pinfunction "2_2") (pintype "passive"))
    )
    (net (code "43") (name "unconnected-(BATT_CONNECT-Pad11)") (class "Default")
      (node (ref "BATT_CONNECT") (pin "11") (pinfunction "11_11") (pintype "passive"))
    )
    (net (code "44") (name "unconnected-(U1-RSV1-PadG4)") (class "Default")
      (node (ref "U1") (pin "G4") (pinfunction "RSV1_G4") (pintype "no_connect"))
    )
    (net (code "45") (name "unconnected-(U1-RSV4-PadB1)") (class "Default")
      (node (ref "U1") (pin "B1") (pinfunction "RSV4_B1") (pintype "no_connect"))
    )
    (net (code "46") (name "unconnected-(U1-RSV5-PadB6)") (class "Default")
      (node (ref "U1") (pin "B6") (pinfunction "RSV5_B6") (pintype "no_connect"))
    )
    (net (code "47") (name "unconnected-(U2-1PPS-Pad18)") (class "Default")
      (node (ref "U2") (pin "18") (pinfunction "1PPS_18") (pintype "output"))
    )
    (net (code "48") (name "unconnected-(U2-CLK-Pad15)") (class "Default")
      (node (ref "U2") (pin "15") (pinfunction "CLK_15") (pintype "input"))
    )
    (net (code "49") (name "unconnected-(U2-CS-Pad20)") (class "Default")
      (node (ref "U2") (pin "20") (pinfunction "CS_20") (pintype "input"))
    )
    (net (code "50") (name "unconnected-(U2-MISO-Pad12)") (class "Default")
      (node (ref "U2") (pin "12") (pinfunction "MISO_12") (pintype "output"))
    )
    (net (code "51") (name "unconnected-(U2-MOSI-Pad14)") (class "Default")
      (node (ref "U2") (pin "14") (pinfunction "MOSI_14") (pintype "input"))
    )
    (net (code "52") (name "unconnected-(U2-~{RESET}-Pad19)") (class "Default")
      (node (ref "U2") (pin "19") (pinfunction "~{RESET}_19") (pintype "input"))
    )
    (net (code "53") (name "unconnected-(U3-AD0{slash}SDO-Pad9)") (class "Default")
      (node (ref "U3") (pin "9") (pinfunction "AD0/SDO_9") (pintype "output"))
    )
    (net (code "54") (name "unconnected-(U3-AUX_CL-Pad7)") (class "Default")
      (node (ref "U3") (pin "7") (pinfunction "AUX_CL_7") (pintype "input"))
    )
    (net (code "55") (name "unconnected-(U3-AUX_DA-Pad21)") (class "Default")
      (node (ref "U3") (pin "21") (pinfunction "AUX_DA_21") (pintype "input"))
    )
    (net (code "56") (name "unconnected-(U3-RESV_19-Pad19)") (class "Default")
      (node (ref "U3") (pin "19") (pinfunction "RESV_19_19") (pintype "passive"))
    )
    (net (code "57") (name "unconnected-(U4-NC-Pad4)") (class "Default")
      (node (ref "U4") (pin "4") (pinfunction "NC_4") (pintype "no_connect"))
    )
  )
)
